# dropout_timer.net
KiCad netlist of a schematic drawn in Altium Designer
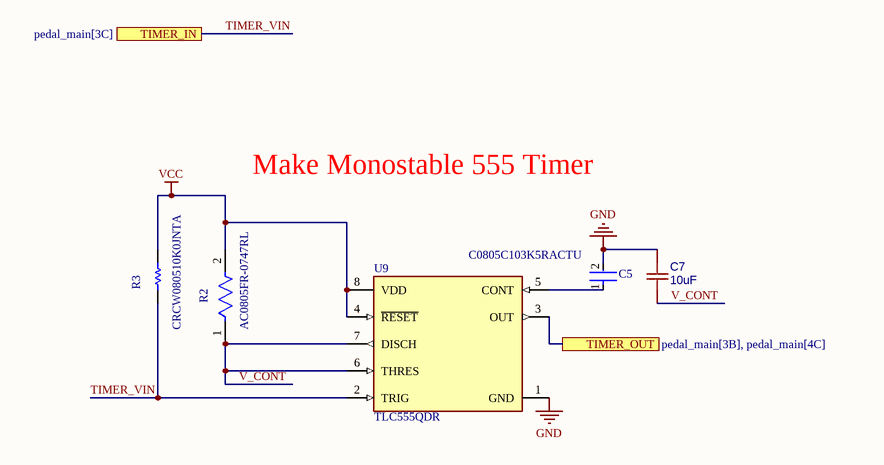
[diagram p0: dropout_timer.SchDoc]

(export (version "E")
  (design (tool "Eeschema 10.0.6"))
  (components
    (comp (ref "C5")
      (value "C0805C103K5RACTU")
      (footprint "FP-C0805C-DN-MFG")
      (description "C0805 10,000 pF X7R 30ppm/°C 10.00% 50 V")
      (fields (field (name "TOLERANCE") "0.1"))
      (libsource (lib "Altium Content Vault") (part "b4654b650e69147ec39a6b967a45e02"))
    )
    (comp (ref "C7")
      (value "10uF")
      (footprint "C0603")
      (libsource (lib "schematic_components") (part "CAP_0603"))
    )
    (comp (ref "R2")
      (value "AC0805FR-0747RL")
      (footprint "FP-AC0805-MFG")
      (description "RES SMD 47 OHM 1% 1/8W 0805")
      (fields
        (field (name "MANUFACTURER") "Yageo")
        (field (name "OCTOPART") "https://octopart.com/ac0805fr-0747rl-yageo-46503502")
      )
      (libsource (lib "Altium Content Vault") (part "1029c3af85768c4190bb7ad29bc67b5"))
    )
    (comp (ref "R3")
      (value "CRCW080510K0JNTA")
      (footprint "RESC2013X50X30LL20T20")
      (fields (field (name "MANUFACTURER") "Vishay Dale"))
      (libsource (lib "Altium Content Vault") (part "RES"))
    )
    (comp (ref "U9")
      (value "TLC555QDR")
      (footprint "FP-D0008A-IPC_C")
      (description "IC OSC SGL TIMER 2.1MHZ 8-SOIC")
      (libsource (lib "Altium Content Vault") (part "d1799b6ad0528f89891d5fcc7aff6db"))
    )
  )
  (nets
    (net (code "1") (name "/TIMER_OUT") (class "Default")
      (node (ref "U9") (pin "3") (pinfunction "OUT_3") (pintype "output"))
    )
    (net (code "2") (name "/TIMER_VIN") (class "Default")
      (node (ref "R3") (pin "1") (pinfunction "1_1") (pintype "passive"))
      (node (ref "U9") (pin "2") (pinfunction "TRIG_2") (pintype "input"))
    )
    (net (code "3") (name "/V_CONT") (class "Default")
      (node (ref "C7") (pin "1") (pinfunction "1_1") (pintype "passive"))
      (node (ref "R2") (pin "1") (pinfunction "1_1") (pintype "passive"))
      (node (ref "U9") (pin "6") (pinfunction "THRES_6") (pintype "input"))
      (node (ref "U9") (pin "7") (pinfunction "DISCH_7") (pintype "output"))
    )
    (net (code "4") (name "GND") (class "Default")
      (node (ref "C5") (pin "2") (pinfunction "2_2") (pintype "passive"))
      (node (ref "C7") (pin "2") (pinfunction "2_2") (pintype "passive"))
      (node (ref "U9") (pin "1") (pinfunction "GND_1") (pintype "power_in"))
    )
    (net (code "5") (name "Net-(U9-CONT)") (class "Default")
      (node (ref "C5") (pin "1") (pinfunction "1_1") (pintype "passive"))
      (node (ref "U9") (pin "5") (pinfunction "CONT_5") (pintype "input"))
    )
    (net (code "6") (name "VCC") (class "Default")
      (node (ref "R2") (pin "2") (pinfunction "2_2") (pintype "passive"))
      (node (ref "R3") (pin "2") (pinfunction "2_2") (pintype "passive"))
      (node (ref "U9") (pin "4") (pinfunction "~{RESET}_4") (pintype "input"))
      (node (ref "U9") (pin "8") (pinfunction "VDD_8") (pintype "power_in"))
    )
  )
)
